# SwitchMatrix__ADG888.net
KiCad netlist of a schematic drawn in EAGLE
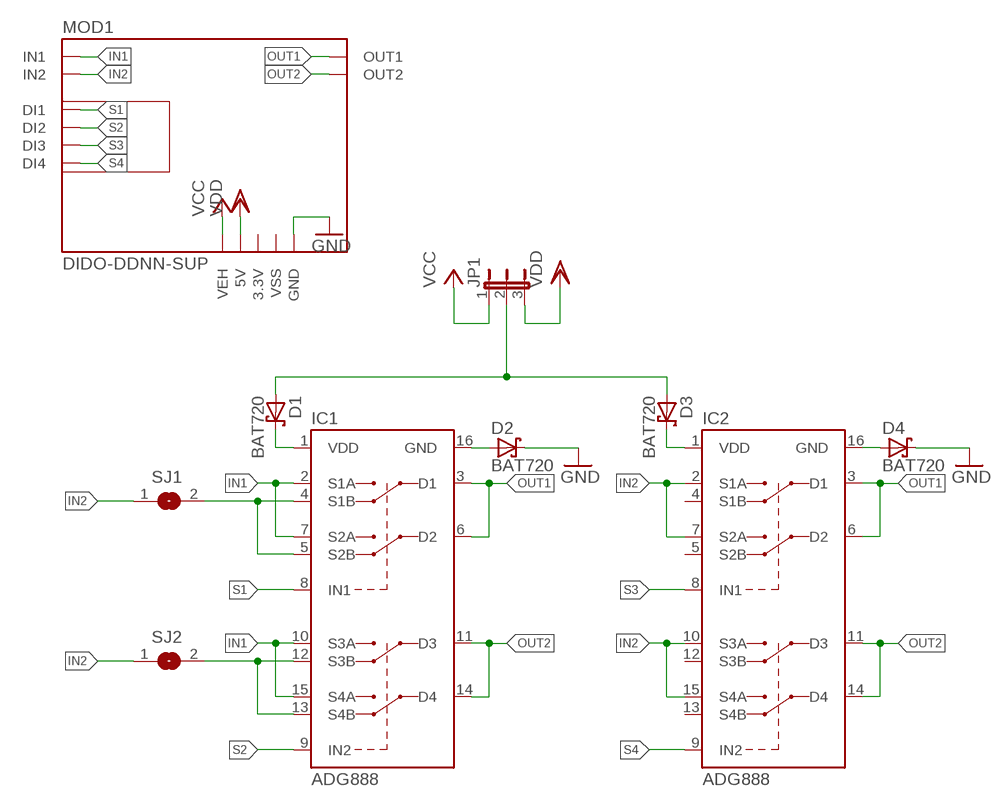
[diagram p0: schematic, sheet 1]

(export (version "E")
  (design (tool "Eeschema 10.0.6"))
  (components
    (comp (ref "D1")
      (value "BAT720")
      (footprint "eagle-import:SOT23")
      (libsource (lib "eagle-import") (part "BAT54"))
    )
    (comp (ref "D2")
      (value "BAT720")
      (footprint "eagle-import:SOT23")
      (libsource (lib "eagle-import") (part "BAT54"))
    )
    (comp (ref "D3")
      (value "BAT720")
      (footprint "eagle-import:SOT23")
      (libsource (lib "eagle-import") (part "BAT54"))
    )
    (comp (ref "D4")
      (value "BAT720")
      (footprint "eagle-import:SOT23")
      (libsource (lib "eagle-import") (part "BAT54"))
    )
    (comp (ref "IC1")
      (value "ADG888")
      (footprint "eagle-import:TSSOP16")
      (libsource (lib "eagle-import") (part "ADG888YRUZ"))
    )
    (comp (ref "IC2")
      (value "ADG888")
      (footprint "eagle-import:TSSOP16")
      (libsource (lib "eagle-import") (part "ADG888YRUZ"))
    )
    (comp (ref "JP1")
      (value "JP2E")
      (footprint "eagle-import:JP2")
      (libsource (lib "eagle-import") (part "JP2E"))
    )
    (comp (ref "MOD1")
      (value "DIDO-DDNN-SUP")
      (footprint "eagle-import:DIDO-DDNN-SUP")
      (libsource (lib "eagle-import") (part "DIDO-DDNN-SUP"))
    )
    (comp (ref "SJ1") (value "SJ") (footprint "eagle-import:SJ") (libsource (lib "eagle-import") (part "SJ")))
    (comp (ref "SJ2") (value "SJ") (footprint "eagle-import:SJ") (libsource (lib "eagle-import") (part "SJ")))
  )
  (nets
    (net (code "1") (name "/3.3V") (class "Default")
      (node (ref "MOD1") (pin "3.3V") (pinfunction "3.3V_3.3V") (pintype "power_in"))
    )
    (net (code "2") (name "/VSS") (class "Default")
      (node (ref "MOD1") (pin "VSS") (pinfunction "VSS_VSS") (pintype "power_in"))
    )
    (net (code "3") (name "GND") (class "Default")
      (node (ref "D2") (pin "3") (pinfunction "C_3") (pintype "passive"))
      (node (ref "D4") (pin "3") (pinfunction "C_3") (pintype "passive"))
      (node (ref "MOD1") (pin "GND1") (pinfunction "GND_GND1") (pintype "power_in"))
      (node (ref "MOD1") (pin "GND2") (pinfunction "GND_GND2") (pintype "power_in"))
      (node (ref "MOD1") (pin "GND3") (pinfunction "GND_GND3") (pintype "power_in"))
      (node (ref "MOD1") (pin "GND4") (pinfunction "GND_GND4") (pintype "power_in"))
    )
    (net (code "4") (name "IN1") (class "Default")
      (node (ref "IC1") (pin "10") (pinfunction "S3A_10") (pintype "bidirectional"))
      (node (ref "IC1") (pin "15") (pinfunction "S4A_15") (pintype "bidirectional"))
      (node (ref "IC1") (pin "2") (pinfunction "S1A_2") (pintype "bidirectional"))
      (node (ref "IC1") (pin "7") (pinfunction "S2A_7") (pintype "bidirectional"))
      (node (ref "MOD1") (pin "IN1_1") (pinfunction "IN1_IN1_1") (pintype "output"))
      (node (ref "MOD1") (pin "IN1_2") (pinfunction "IN1_IN1_2") (pintype "output"))
      (node (ref "MOD1") (pin "IN1_3") (pinfunction "IN1_IN1_3") (pintype "output"))
      (node (ref "MOD1") (pin "IN1_4") (pinfunction "IN1_IN1_4") (pintype "output"))
    )
    (net (code "5") (name "IN2") (class "Default")
      (node (ref "IC2") (pin "10") (pinfunction "S3A_10") (pintype "bidirectional"))
      (node (ref "IC2") (pin "15") (pinfunction "S4A_15") (pintype "bidirectional"))
      (node (ref "IC2") (pin "2") (pinfunction "S1A_2") (pintype "bidirectional"))
      (node (ref "IC2") (pin "7") (pinfunction "S2A_7") (pintype "bidirectional"))
      (node (ref "MOD1") (pin "IN2_1") (pinfunction "IN2_IN2_1") (pintype "output"))
      (node (ref "MOD1") (pin "IN2_2") (pinfunction "IN2_IN2_2") (pintype "output"))
      (node (ref "MOD1") (pin "IN2_3") (pinfunction "IN2_IN2_3") (pintype "output"))
      (node (ref "MOD1") (pin "IN2_4") (pinfunction "IN2_IN2_4") (pintype "output"))
      (node (ref "SJ1") (pin "1") (pinfunction "1_1") (pintype "passive"))
      (node (ref "SJ2") (pin "1") (pinfunction "1_1") (pintype "passive"))
    )
    (net (code "6") (name "Net-(D1-A)") (class "Default")
      (node (ref "D1") (pin "1") (pinfunction "A_1") (pintype "passive"))
      (node (ref "D3") (pin "1") (pinfunction "A_1") (pintype "passive"))
      (node (ref "JP1") (pin "2") (pinfunction "2_2") (pintype "passive"))
    )
    (net (code "7") (name "Net-(D1-C)") (class "Default")
      (node (ref "D1") (pin "3") (pinfunction "C_3") (pintype "passive"))
      (node (ref "IC1") (pin "1") (pinfunction "VDD_1") (pintype "power_in"))
    )
    (net (code "8") (name "Net-(D2-A)") (class "Default")
      (node (ref "D2") (pin "1") (pinfunction "A_1") (pintype "passive"))
      (node (ref "IC1") (pin "16") (pinfunction "GND_16") (pintype "power_in"))
    )
    (net (code "9") (name "Net-(D3-C)") (class "Default")
      (node (ref "D3") (pin "3") (pinfunction "C_3") (pintype "passive"))
      (node (ref "IC2") (pin "1") (pinfunction "VDD_1") (pintype "power_in"))
    )
    (net (code "10") (name "Net-(D4-A)") (class "Default")
      (node (ref "D4") (pin "1") (pinfunction "A_1") (pintype "passive"))
      (node (ref "IC2") (pin "16") (pinfunction "GND_16") (pintype "power_in"))
    )
    (net (code "11") (name "Net-(IC1-S1B)") (class "Default")
      (node (ref "IC1") (pin "4") (pinfunction "S1B_4") (pintype "bidirectional"))
      (node (ref "IC1") (pin "5") (pinfunction "S2B_5") (pintype "bidirectional"))
      (node (ref "SJ1") (pin "2") (pinfunction "2_2") (pintype "passive"))
    )
    (net (code "12") (name "Net-(IC1-S3B)") (class "Default")
      (node (ref "IC1") (pin "12") (pinfunction "S3B_12") (pintype "bidirectional"))
      (node (ref "IC1") (pin "13") (pinfunction "S4B_13") (pintype "bidirectional"))
      (node (ref "SJ2") (pin "2") (pinfunction "2_2") (pintype "passive"))
    )
    (net (code "13") (name "OUT1") (class "Default")
      (node (ref "IC1") (pin "3") (pinfunction "D1_3") (pintype "bidirectional"))
      (node (ref "IC1") (pin "6") (pinfunction "D2_6") (pintype "bidirectional"))
      (node (ref "IC2") (pin "3") (pinfunction "D1_3") (pintype "bidirectional"))
      (node (ref "IC2") (pin "6") (pinfunction "D2_6") (pintype "bidirectional"))
      (node (ref "MOD1") (pin "OUT1_1") (pinfunction "OUT1_OUT1_1") (pintype "input"))
      (node (ref "MOD1") (pin "OUT1_2") (pinfunction "OUT1_OUT1_2") (pintype "input"))
      (node (ref "MOD1") (pin "OUT1_3") (pinfunction "OUT1_OUT1_3") (pintype "input"))
      (node (ref "MOD1") (pin "OUT1_4") (pinfunction "OUT1_OUT1_4") (pintype "input"))
    )
    (net (code "14") (name "OUT2") (class "Default")
      (node (ref "IC1") (pin "11") (pinfunction "D3_11") (pintype "bidirectional"))
      (node (ref "IC1") (pin "14") (pinfunction "D4_14") (pintype "bidirectional"))
      (node (ref "IC2") (pin "11") (pinfunction "D3_11") (pintype "bidirectional"))
      (node (ref "IC2") (pin "14") (pinfunction "D4_14") (pintype "bidirectional"))
      (node (ref "MOD1") (pin "OUT2_1") (pinfunction "OUT2_OUT2_1") (pintype "input"))
      (node (ref "MOD1") (pin "OUT2_2") (pinfunction "OUT2_OUT2_2") (pintype "input"))
      (node (ref "MOD1") (pin "OUT2_3") (pinfunction "OUT2_OUT2_3") (pintype "input"))
      (node (ref "MOD1") (pin "OUT2_4") (pinfunction "OUT2_OUT2_4") (pintype "input"))
    )
    (net (code "15") (name "S1") (class "Default")
      (node (ref "IC1") (pin "8") (pinfunction "IN1_8") (pintype "input"))
      (node (ref "MOD1") (pin "DI1") (pinfunction "DI1_DI1") (pintype "output"))
    )
    (net (code "16") (name "S2") (class "Default")
      (node (ref "IC1") (pin "9") (pinfunction "IN2_9") (pintype "input"))
      (node (ref "MOD1") (pin "DI2") (pinfunction "DI2_DI2") (pintype "output"))
    )
    (net (code "17") (name "S3") (class "Default")
      (node (ref "IC2") (pin "8") (pinfunction "IN1_8") (pintype "input"))
      (node (ref "MOD1") (pin "DI3") (pinfunction "DI3_DI3") (pintype "output"))
    )
    (net (code "18") (name "S4") (class "Default")
      (node (ref "IC2") (pin "9") (pinfunction "IN2_9") (pintype "input"))
      (node (ref "MOD1") (pin "DI4") (pinfunction "DI4_DI4") (pintype "output"))
    )
    (net (code "19") (name "VCC") (class "Default")
      (node (ref "JP1") (pin "1") (pinfunction "1_1") (pintype "passive"))
      (node (ref "MOD1") (pin "VEH") (pinfunction "VEH_VEH") (pintype "power_in"))
    )
    (net (code "20") (name "VDD") (class "Default")
      (node (ref "JP1") (pin "3") (pinfunction "3_3") (pintype "passive"))
      (node (ref "MOD1") (pin "5V") (pinfunction "5V_5V") (pintype "power_in"))
    )
    (net (code "21") (name "unconnected-(IC2-S1B-Pad4)") (class "Default")
      (node (ref "IC2") (pin "4") (pinfunction "S1B_4") (pintype "bidirectional"))
    )
    (net (code "22") (name "unconnected-(IC2-S2B-Pad5)") (class "Default")
      (node (ref "IC2") (pin "5") (pinfunction "S2B_5") (pintype "bidirectional"))
    )
    (net (code "23") (name "unconnected-(IC2-S3B-Pad12)") (class "Default")
      (node (ref "IC2") (pin "12") (pinfunction "S3B_12") (pintype "bidirectional"))
    )
    (net (code "24") (name "unconnected-(IC2-S4B-Pad13)") (class "Default")
      (node (ref "IC2") (pin "13") (pinfunction "S4B_13") (pintype "bidirectional"))
    )
  )
)
